# Fan_Controller_v1_0.net
KiCad netlist of a schematic drawn in EAGLE
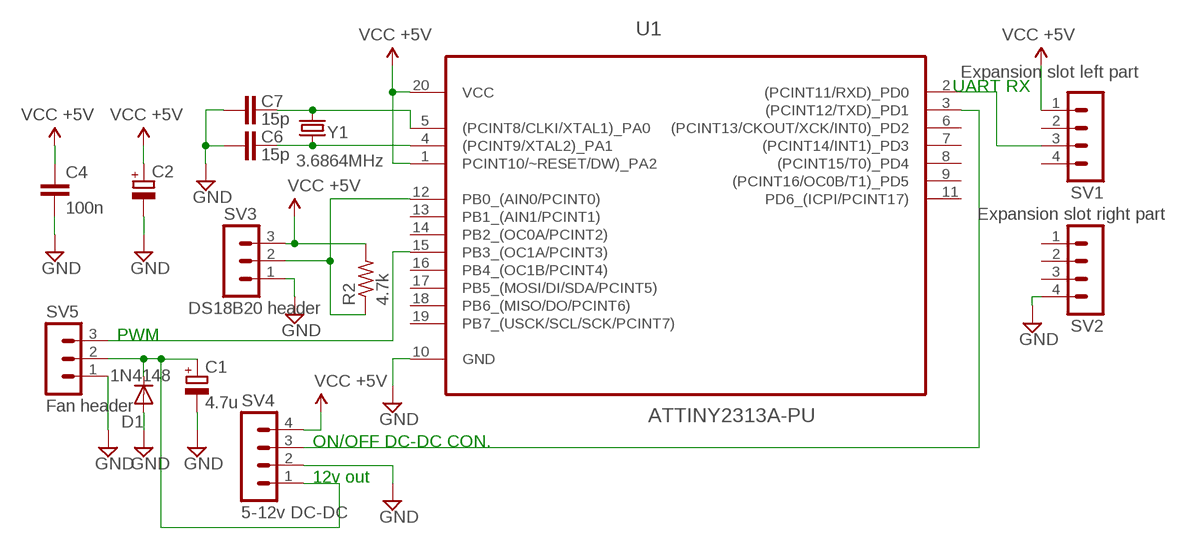
[diagram p0: schematic, sheet 1]

(export (version "E")
  (design (tool "Eeschema 10.0.6"))
  (components
    (comp (ref "C1")
      (value "4.7u")
      (footprint "eagle-import:E2,5-6E")
      (libsource (lib "eagle-import") (part "CPOL-EUE2,5-6E"))
    )
    (comp (ref "C2")
      (value "CPOL-EUE5-6")
      (footprint "eagle-import:E5-6")
      (libsource (lib "eagle-import") (part "CPOL-EUE5-6"))
    )
    (comp (ref "C4")
      (value "100n")
      (footprint "eagle-import:C0805K")
      (libsource (lib "eagle-import") (part "C-EUC0805K"))
    )
    (comp (ref "C6")
      (value "15p")
      (footprint "eagle-import:C0805K")
      (libsource (lib "eagle-import") (part "C-EUC0805K"))
    )
    (comp (ref "C7")
      (value "15p")
      (footprint "eagle-import:C0805K")
      (libsource (lib "eagle-import") (part "C-EUC0805K"))
    )
    (comp (ref "D1")
      (value "1N4148")
      (footprint "eagle-import:DO35-7")
      (libsource (lib "eagle-import") (part "1N4148DO35-7"))
    )
    (comp (ref "R2")
      (value "4.7k")
      (footprint "eagle-import:R1206")
      (libsource (lib "eagle-import") (part "R-US_R1206"))
    )
    (comp (ref "SV1")
      (value "Expansion slot left part")
      (footprint "eagle-import:MA04-1")
      (libsource (lib "eagle-import") (part "MA04-1"))
    )
    (comp (ref "SV2")
      (value "Expansion slot right part")
      (footprint "eagle-import:MA04-1")
      (libsource (lib "eagle-import") (part "MA04-1"))
    )
    (comp (ref "SV3")
      (value "DS18B20 header")
      (footprint "eagle-import:MA03-1")
      (libsource (lib "eagle-import") (part "MA03-1"))
    )
    (comp (ref "SV4")
      (value "5-12v DC-DC")
      (footprint "eagle-import:MA04-1")
      (libsource (lib "eagle-import") (part "MA04-1"))
    )
    (comp (ref "SV5")
      (value "Fan header")
      (footprint "eagle-import:MA03-1")
      (libsource (lib "eagle-import") (part "MA03-1"))
    )
    (comp (ref "U1")
      (value "ATTINY2313A-PU")
      (footprint "eagle-import:DIP254P762X533-20")
      (libsource (lib "eagle-import") (part "ATTINY2313A-PU"))
    )
    (comp (ref "Y1")
      (value "3.6864MHz")
      (footprint "eagle-import:HC49U-V")
      (libsource (lib "eagle-import") (part "CRYSTALHC49UV"))
    )
  )
  (nets
    (net (code "1") (name "GND") (class "Default")
      (node (ref "C1") (pin "-") (pinfunction "-_-") (pintype "passive"))
      (node (ref "C2") (pin "-") (pinfunction "-_-") (pintype "passive"))
      (node (ref "C4") (pin "2") (pinfunction "2_2") (pintype "passive"))
      (node (ref "C6") (pin "2") (pinfunction "2_2") (pintype "passive"))
      (node (ref "C7") (pin "2") (pinfunction "2_2") (pintype "passive"))
      (node (ref "D1") (pin "A") (pinfunction "A_A") (pintype "passive"))
      (node (ref "SV2") (pin "4") (pinfunction "4_4") (pintype "passive"))
      (node (ref "SV3") (pin "1") (pinfunction "1_1") (pintype "passive"))
      (node (ref "SV4") (pin "2") (pinfunction "2_2") (pintype "passive"))
      (node (ref "SV5") (pin "1") (pinfunction "1_1") (pintype "passive"))
      (node (ref "U1") (pin "10") (pinfunction "GND_10") (pintype "passive"))
    )
    (net (code "2") (name "Net-(C1-Pad+)") (class "Default")
      (node (ref "C1") (pin "+") (pinfunction "+_+") (pintype "passive"))
      (node (ref "D1") (pin "C") (pinfunction "C_C") (pintype "passive"))
      (node (ref "SV4") (pin "1") (pinfunction "1_1") (pintype "passive"))
      (node (ref "SV5") (pin "2") (pinfunction "2_2") (pintype "passive"))
    )
    (net (code "3") (name "Net-(U1-(PCINT8{slash}CLKI{slash}XTAL1)_PA0)") (class "Default")
      (node (ref "C7") (pin "1") (pinfunction "1_1") (pintype "passive"))
      (node (ref "U1") (pin "5") (pinfunction "(PCINT8/CLKI/XTAL1)_PA0_5") (pintype "bidirectional"))
      (node (ref "Y1") (pin "2") (pinfunction "2_2") (pintype "passive"))
    )
    (net (code "4") (name "Net-(U1-(PCINT9{slash}XTAL2)_PA1)") (class "Default")
      (node (ref "C6") (pin "1") (pinfunction "1_1") (pintype "passive"))
      (node (ref "U1") (pin "4") (pinfunction "(PCINT9/XTAL2)_PA1_4") (pintype "bidirectional"))
      (node (ref "Y1") (pin "1") (pinfunction "1_1") (pintype "passive"))
    )
    (net (code "5") (name "Net-(U1-(PCINT11{slash}RXD)_PD0)") (class "Default")
      (node (ref "SV1") (pin "3") (pinfunction "3_3") (pintype "passive"))
      (node (ref "U1") (pin "2") (pinfunction "(PCINT11/RXD)_PD0_2") (pintype "bidirectional"))
    )
    (net (code "6") (name "Net-(U1-(PCINT12{slash}TXD)_PD1)") (class "Default")
      (node (ref "SV4") (pin "3") (pinfunction "3_3") (pintype "passive"))
      (node (ref "U1") (pin "3") (pinfunction "(PCINT12/TXD)_PD1_3") (pintype "bidirectional"))
    )
    (net (code "7") (name "Net-(U1-PB0_(AIN0{slash}PCINT0))") (class "Default")
      (node (ref "R2") (pin "1") (pinfunction "1_1") (pintype "passive"))
      (node (ref "SV3") (pin "2") (pinfunction "2_2") (pintype "passive"))
      (node (ref "U1") (pin "12") (pinfunction "PB0_(AIN0/PCINT0)_12") (pintype "bidirectional"))
    )
    (net (code "8") (name "Net-(U1-PB3_(OC1A{slash}PCINT3))") (class "Default")
      (node (ref "SV5") (pin "3") (pinfunction "3_3") (pintype "passive"))
      (node (ref "U1") (pin "15") (pinfunction "PB3_(OC1A/PCINT3)_15") (pintype "bidirectional"))
    )
    (net (code "9") (name "VCC +5V") (class "Default")
      (node (ref "C2") (pin "+") (pinfunction "+_+") (pintype "passive"))
      (node (ref "C4") (pin "1") (pinfunction "1_1") (pintype "passive"))
      (node (ref "R2") (pin "2") (pinfunction "2_2") (pintype "passive"))
      (node (ref "SV1") (pin "1") (pinfunction "1_1") (pintype "passive"))
      (node (ref "SV3") (pin "3") (pinfunction "3_3") (pintype "passive"))
      (node (ref "SV4") (pin "4") (pinfunction "4_4") (pintype "passive"))
      (node (ref "U1") (pin "1") (pinfunction "PCINT10/~{RESET/DW})_PA2_1") (pintype "bidirectional"))
      (node (ref "U1") (pin "20") (pinfunction "VCC_20") (pintype "power_in"))
    )
    (net (code "10") (name "unconnected-(SV1-Pad2)") (class "Default")
      (node (ref "SV1") (pin "2") (pinfunction "2_2") (pintype "passive"))
    )
    (net (code "11") (name "unconnected-(SV1-Pad4)") (class "Default")
      (node (ref "SV1") (pin "4") (pinfunction "4_4") (pintype "passive"))
    )
    (net (code "12") (name "unconnected-(SV2-Pad1)") (class "Default")
      (node (ref "SV2") (pin "1") (pinfunction "1_1") (pintype "passive"))
    )
    (net (code "13") (name "unconnected-(SV2-Pad2)") (class "Default")
      (node (ref "SV2") (pin "2") (pinfunction "2_2") (pintype "passive"))
    )
    (net (code "14") (name "unconnected-(SV2-Pad3)") (class "Default")
      (node (ref "SV2") (pin "3") (pinfunction "3_3") (pintype "passive"))
    )
    (net (code "15") (name "unconnected-(U1-(PCINT13{slash}CKOUT{slash}XCK{slash}INT0)_PD2-Pad6)") (class "Default")
      (node (ref "U1") (pin "6") (pinfunction "(PCINT13/CKOUT/XCK/INT0)_PD2_6") (pintype "bidirectional"))
    )
    (net (code "16") (name "unconnected-(U1-(PCINT14{slash}INT1)_PD3-Pad7)") (class "Default")
      (node (ref "U1") (pin "7") (pinfunction "(PCINT14/INT1)_PD3_7") (pintype "bidirectional"))
    )
    (net (code "17") (name "unconnected-(U1-(PCINT15{slash}T0)_PD4-Pad8)") (class "Default")
      (node (ref "U1") (pin "8") (pinfunction "(PCINT15/T0)_PD4_8") (pintype "bidirectional"))
    )
    (net (code "18") (name "unconnected-(U1-(PCINT16{slash}OC0B{slash}T1)_PD5-Pad9)") (class "Default")
      (node (ref "U1") (pin "9") (pinfunction "(PCINT16/OC0B/T1)_PD5_9") (pintype "bidirectional"))
    )
    (net (code "19") (name "unconnected-(U1-PB1_(AIN1{slash}PCINT1)-Pad13)") (class "Default")
      (node (ref "U1") (pin "13") (pinfunction "PB1_(AIN1/PCINT1)_13") (pintype "bidirectional"))
    )
    (net (code "20") (name "unconnected-(U1-PB2_(OC0A{slash}PCINT2)-Pad14)") (class "Default")
      (node (ref "U1") (pin "14") (pinfunction "PB2_(OC0A/PCINT2)_14") (pintype "bidirectional"))
    )
    (net (code "21") (name "unconnected-(U1-PB4_(OC1B{slash}PCINT4)-Pad16)") (class "Default")
      (node (ref "U1") (pin "16") (pinfunction "PB4_(OC1B/PCINT4)_16") (pintype "bidirectional"))
    )
    (net (code "22") (name "unconnected-(U1-PB5_(MOSI{slash}DI{slash}SDA{slash}PCINT5)-Pad17)") (class "Default")
      (node (ref "U1") (pin "17") (pinfunction "PB5_(MOSI/DI/SDA/PCINT5)_17") (pintype "bidirectional"))
    )
    (net (code "23") (name "unconnected-(U1-PB6_(MISO{slash}DO{slash}PCINT6)-Pad18)") (class "Default")
      (node (ref "U1") (pin "18") (pinfunction "PB6_(MISO/DO/PCINT6)_18") (pintype "bidirectional"))
    )
    (net (code "24") (name "unconnected-(U1-PB7_(USCK{slash}SCL{slash}SCK{slash}PCINT7)-Pad19)") (class "Default")
      (node (ref "U1") (pin "19") (pinfunction "PB7_(USCK/SCL/SCK/PCINT7)_19") (pintype "bidirectional"))
    )
    (net (code "25") (name "unconnected-(U1-PD6_(ICPI{slash}PCINT17)-Pad11)") (class "Default")
      (node (ref "U1") (pin "11") (pinfunction "PD6_(ICPI/PCINT17)_11") (pintype "bidirectional"))
    )
  )
)
